# Arduino-Pro-v16_No-Silk.net
KiCad netlist of a schematic drawn in EAGLE
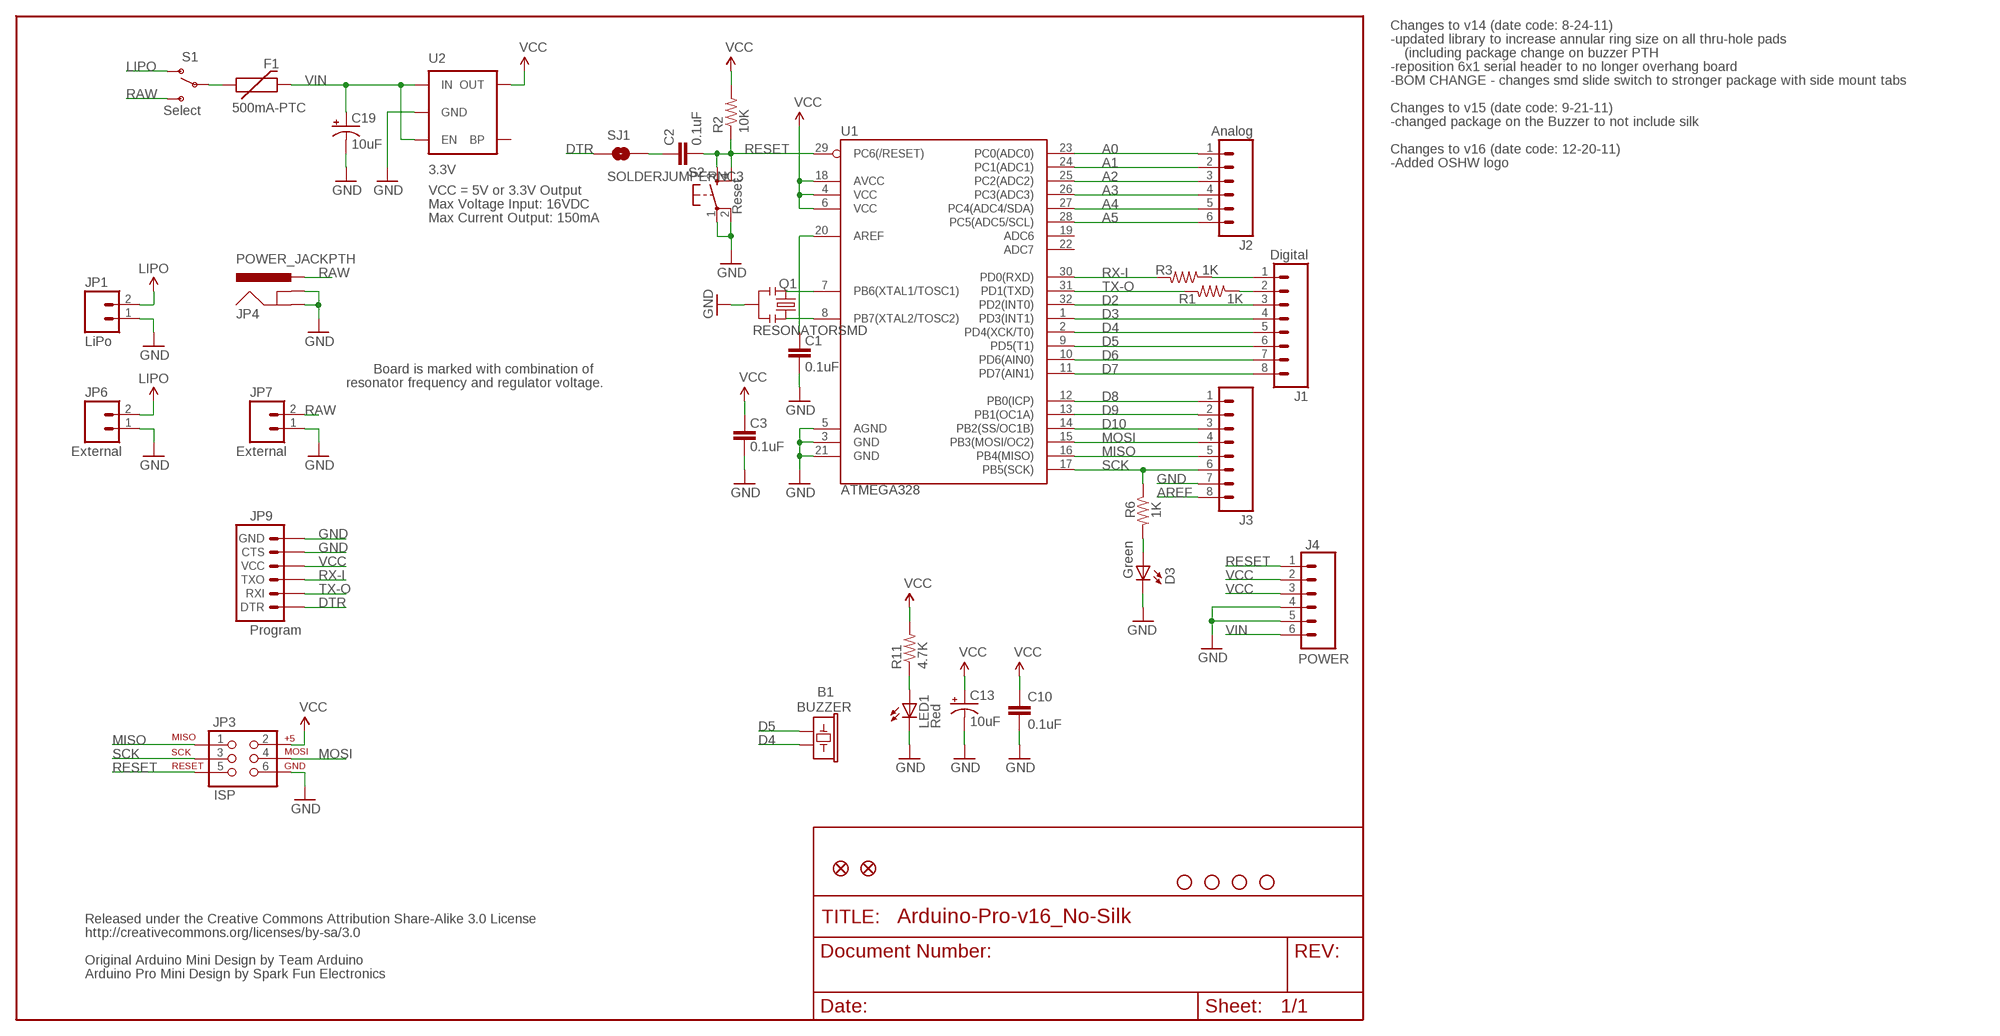
[diagram p0: schematic, sheet 1]

(export (version "E")
  (design (tool "Eeschema 10.0.6"))
  (components
    (comp (ref "B1")
      (value "BUZZER")
      (footprint "eagle-import:BUZZER-12MM-NS-KIT")
      (libsource (lib "eagle-import") (part "BUZZERPTH-NS-KIT"))
    )
    (comp (ref "C1")
      (value "0.1uF")
      (footprint "eagle-import:0402-CAP")
      (libsource (lib "eagle-import") (part "CAP0402-CAP"))
    )
    (comp (ref "C2")
      (value "0.1uF")
      (footprint "eagle-import:0402-CAP")
      (libsource (lib "eagle-import") (part "CAP0402-CAP"))
    )
    (comp (ref "C3")
      (value "0.1uF")
      (footprint "eagle-import:0402-CAP")
      (libsource (lib "eagle-import") (part "CAP0402-CAP"))
    )
    (comp (ref "C10")
      (value "0.1uF")
      (footprint "eagle-import:0402-CAP")
      (libsource (lib "eagle-import") (part "CAP0402-CAP"))
    )
    (comp (ref "C13")
      (value "10uF")
      (footprint "eagle-import:EIA3216")
      (libsource (lib "eagle-import") (part "CAP_POL1206"))
    )
    (comp (ref "C19")
      (value "10uF")
      (footprint "eagle-import:EIA3216")
      (libsource (lib "eagle-import") (part "CAP_POL1206"))
    )
    (comp (ref "D3")
      (value "Green")
      (footprint "eagle-import:LED-0603")
      (libsource (lib "eagle-import") (part "LED0603"))
    )
    (comp (ref "F1")
      (value "500mA-PTC")
      (footprint "eagle-import:PTC-1206")
      (libsource (lib "eagle-import") (part "PTCSMD"))
    )
    (comp (ref "J1")
      (value "Digital")
      (footprint "eagle-import:1X08")
      (libsource (lib "eagle-import") (part "M081X08"))
    )
    (comp (ref "J2")
      (value "Analog")
      (footprint "eagle-import:1X06")
      (libsource (lib "eagle-import") (part "M06SIP"))
    )
    (comp (ref "J3")
      (value "M081X08")
      (footprint "eagle-import:1X08")
      (libsource (lib "eagle-import") (part "M081X08"))
    )
    (comp (ref "J4")
      (value "POWER")
      (footprint "eagle-import:1X06")
      (libsource (lib "eagle-import") (part "M06SIP"))
    )
    (comp (ref "JP1")
      (value "LiPo")
      (footprint "eagle-import:JST-2-SMD")
      (libsource (lib "eagle-import") (part "M02-JST-2MM-SMT"))
    )
    (comp (ref "JP2")
      (value "FIDUCIAL1X2.5")
      (footprint "eagle-import:FIDUCIAL-1X2.5")
      (libsource (lib "eagle-import") (part "FIDUCIAL1X2.5"))
    )
    (comp (ref "JP3")
      (value "ISP")
      (footprint "eagle-import:2X3")
      (libsource (lib "eagle-import") (part "AVR_SPI_PRG_6PTH"))
    )
    (comp (ref "JP4")
      (value "POWER_JACKPTH")
      (footprint "eagle-import:POWER_JACK_PTH")
      (libsource (lib "eagle-import") (part "POWER_JACKPTH"))
    )
    (comp (ref "JP5")
      (value "FIDUCIAL1X2.5")
      (footprint "eagle-import:FIDUCIAL-1X2.5")
      (libsource (lib "eagle-import") (part "FIDUCIAL1X2.5"))
    )
    (comp (ref "JP6")
      (value "External")
      (footprint "eagle-import:1X02")
      (libsource (lib "eagle-import") (part "M02PTH"))
    )
    (comp (ref "JP7")
      (value "External")
      (footprint "eagle-import:1X02")
      (libsource (lib "eagle-import") (part "M02PTH"))
    )
    (comp (ref "JP9")
      (value "Program")
      (footprint "eagle-import:1X06-SMD")
      (libsource (lib "eagle-import") (part "ARDUINO_SERIAL_PROGRAMSMD"))
    )
    (comp (ref "LED1")
      (value "Red")
      (footprint "eagle-import:LED-0603")
      (libsource (lib "eagle-import") (part "LED0603"))
    )
    (comp (ref "Q1")
      (value "RESONATORSMD")
      (footprint "eagle-import:RESONATOR-SMD")
      (libsource (lib "eagle-import") (part "RESONATORSMD"))
    )
    (comp (ref "R1")
      (value "1K")
      (footprint "eagle-import:0402-RES")
      (libsource (lib "eagle-import") (part "RESISTOR0402-RES"))
    )
    (comp (ref "R2")
      (value "10K")
      (footprint "eagle-import:0402-RES")
      (libsource (lib "eagle-import") (part "RESISTOR0402-RES"))
    )
    (comp (ref "R3")
      (value "1K")
      (footprint "eagle-import:0402-RES")
      (libsource (lib "eagle-import") (part "RESISTOR0402-RES"))
    )
    (comp (ref "R6")
      (value "1K")
      (footprint "eagle-import:0402-RES")
      (libsource (lib "eagle-import") (part "RESISTOR0402-RES"))
    )
    (comp (ref "R11")
      (value "4.7K")
      (footprint "eagle-import:0402-RES")
      (libsource (lib "eagle-import") (part "RESISTOR0402-RES"))
    )
    (comp (ref "S1")
      (value "Select")
      (footprint "eagle-import:SWITCH-SPST-SMD-A")
      (libsource (lib "eagle-import") (part "SWITCH-SPST-SMD-A"))
    )
    (comp (ref "S2")
      (value "Reset")
      (footprint "eagle-import:TACTILE_SWITCH_SMD")
      (libsource (lib "eagle-import") (part "TAC_SWITCHSMD"))
    )
    (comp (ref "SJ1")
      (value "SOLDERJUMPERNC3")
      (footprint "eagle-import:SJ_2S-NOTRACE")
      (libsource (lib "eagle-import") (part "SOLDERJUMPERNC2"))
    )
    (comp (ref "U$1")
      (value "STAND-OFF")
      (footprint "eagle-import:STAND-OFF")
      (libsource (lib "eagle-import") (part "STAND-OFF"))
    )
    (comp (ref "U$3")
      (value "STAND-OFF")
      (footprint "eagle-import:STAND-OFF")
      (libsource (lib "eagle-import") (part "STAND-OFF"))
    )
    (comp (ref "U$9")
      (value "STAND-OFF")
      (footprint "eagle-import:STAND-OFF")
      (libsource (lib "eagle-import") (part "STAND-OFF"))
    )
    (comp (ref "U$10")
      (value "STAND-OFF")
      (footprint "eagle-import:STAND-OFF")
      (libsource (lib "eagle-import") (part "STAND-OFF"))
    )
    (comp (ref "U1")
      (value "ATMEGA328")
      (footprint "eagle-import:TQFP32-08")
      (libsource (lib "eagle-import") (part "ATMEGA168"))
    )
    (comp (ref "U2")
      (value "3.3V")
      (footprint "eagle-import:SOT23-5")
      (libsource (lib "eagle-import") (part "V_REG_LDOSMD"))
    )
  )
  (nets
    (net (code "1") (name "/A0") (class "Default")
      (node (ref "J2") (pin "1") (pinfunction "1_1") (pintype "passive"))
      (node (ref "U1") (pin "23") (pinfunction "PC0(ADC0)_23") (pintype "bidirectional"))
    )
    (net (code "2") (name "/A1") (class "Default")
      (node (ref "J2") (pin "2") (pinfunction "2_2") (pintype "passive"))
      (node (ref "U1") (pin "24") (pinfunction "PC1(ADC1)_24") (pintype "bidirectional"))
    )
    (net (code "3") (name "/A2") (class "Default")
      (node (ref "J2") (pin "3") (pinfunction "3_3") (pintype "passive"))
      (node (ref "U1") (pin "25") (pinfunction "PC2(ADC2)_25") (pintype "bidirectional"))
    )
    (net (code "4") (name "/A3") (class "Default")
      (node (ref "J2") (pin "4") (pinfunction "4_4") (pintype "passive"))
      (node (ref "U1") (pin "26") (pinfunction "PC3(ADC3)_26") (pintype "bidirectional"))
    )
    (net (code "5") (name "/A4") (class "Default")
      (node (ref "J2") (pin "5") (pinfunction "5_5") (pintype "passive"))
      (node (ref "U1") (pin "27") (pinfunction "PC4(ADC4/SDA)_27") (pintype "bidirectional"))
    )
    (net (code "6") (name "/A5") (class "Default")
      (node (ref "J2") (pin "6") (pinfunction "6_6") (pintype "passive"))
      (node (ref "U1") (pin "28") (pinfunction "PC5(ADC5/SCL)_28") (pintype "bidirectional"))
    )
    (net (code "7") (name "/AREF") (class "Default")
      (node (ref "C1") (pin "2") (pinfunction "2_2") (pintype "passive"))
      (node (ref "J3") (pin "8") (pinfunction "8_8") (pintype "passive"))
      (node (ref "U1") (pin "20") (pinfunction "AREF_20") (pintype "bidirectional"))
    )
    (net (code "8") (name "/D2") (class "Default")
      (node (ref "J1") (pin "3") (pinfunction "3_3") (pintype "passive"))
      (node (ref "U1") (pin "32") (pinfunction "PD2(INT0)_32") (pintype "bidirectional"))
    )
    (net (code "9") (name "/D3") (class "Default")
      (node (ref "J1") (pin "4") (pinfunction "4_4") (pintype "passive"))
      (node (ref "U1") (pin "1") (pinfunction "PD3(INT1)_1") (pintype "bidirectional"))
    )
    (net (code "10") (name "/D4") (class "Default")
      (node (ref "B1") (pin "-") (pinfunction "2_-") (pintype "passive"))
      (node (ref "J1") (pin "5") (pinfunction "5_5") (pintype "passive"))
      (node (ref "U1") (pin "2") (pinfunction "PD4(XCK/T0)_2") (pintype "bidirectional"))
    )
    (net (code "11") (name "/D5") (class "Default")
      (node (ref "B1") (pin "+") (pinfunction "1_+") (pintype "passive"))
      (node (ref "J1") (pin "6") (pinfunction "6_6") (pintype "passive"))
      (node (ref "U1") (pin "9") (pinfunction "PD5(T1)_9") (pintype "bidirectional"))
    )
    (net (code "12") (name "/D6") (class "Default")
      (node (ref "J1") (pin "7") (pinfunction "7_7") (pintype "passive"))
      (node (ref "U1") (pin "10") (pinfunction "PD6(AIN0)_10") (pintype "bidirectional"))
    )
    (net (code "13") (name "/D7") (class "Default")
      (node (ref "J1") (pin "8") (pinfunction "8_8") (pintype "passive"))
      (node (ref "U1") (pin "11") (pinfunction "PD7(AIN1)_11") (pintype "bidirectional"))
    )
    (net (code "14") (name "/D8") (class "Default")
      (node (ref "J3") (pin "1") (pinfunction "1_1") (pintype "passive"))
      (node (ref "U1") (pin "12") (pinfunction "PB0(ICP)_12") (pintype "bidirectional"))
    )
    (net (code "15") (name "/D9") (class "Default")
      (node (ref "J3") (pin "2") (pinfunction "2_2") (pintype "passive"))
      (node (ref "U1") (pin "13") (pinfunction "PB1(OC1A)_13") (pintype "bidirectional"))
    )
    (net (code "16") (name "/D10") (class "Default")
      (node (ref "J3") (pin "3") (pinfunction "3_3") (pintype "passive"))
      (node (ref "U1") (pin "14") (pinfunction "PB2(SS/OC1B)_14") (pintype "bidirectional"))
    )
    (net (code "17") (name "/DTR") (class "Default")
      (node (ref "JP9") (pin "1") (pinfunction "DTR_1") (pintype "passive"))
      (node (ref "SJ1") (pin "1") (pinfunction "1_1") (pintype "passive"))
    )
    (net (code "18") (name "/MISO") (class "Default")
      (node (ref "J3") (pin "5") (pinfunction "5_5") (pintype "passive"))
      (node (ref "JP3") (pin "1") (pinfunction "1_1") (pintype "passive"))
      (node (ref "U1") (pin "16") (pinfunction "PB4(MISO)_16") (pintype "bidirectional"))
    )
    (net (code "19") (name "/MOSI") (class "Default")
      (node (ref "J3") (pin "4") (pinfunction "4_4") (pintype "passive"))
      (node (ref "JP3") (pin "4") (pinfunction "4_4") (pintype "passive"))
      (node (ref "U1") (pin "15") (pinfunction "PB3(MOSI/OC2)_15") (pintype "bidirectional"))
    )
    (net (code "20") (name "/RAW") (class "Default")
      (node (ref "JP4") (pin "PWR") (pinfunction "PWR_PWR") (pintype "bidirectional"))
      (node (ref "JP7") (pin "2") (pinfunction "2_2") (pintype "passive"))
      (node (ref "S1") (pin "3") (pinfunction "S_3") (pintype "passive"))
    )
    (net (code "21") (name "/RESET") (class "Default")
      (node (ref "C2") (pin "2") (pinfunction "2_2") (pintype "passive"))
      (node (ref "J4") (pin "1") (pinfunction "1_1") (pintype "passive"))
      (node (ref "JP3") (pin "5") (pinfunction "5_5") (pintype "passive"))
      (node (ref "R2") (pin "1") (pinfunction "1_1") (pintype "passive"))
      (node (ref "S2") (pin "3") (pinfunction "3_3") (pintype "passive"))
      (node (ref "S2") (pin "4") (pinfunction "4_4") (pintype "passive"))
      (node (ref "U1") (pin "29") (pinfunction "PC6(/RESET)_29") (pintype "bidirectional"))
    )
    (net (code "22") (name "/RX-I") (class "Default")
      (node (ref "JP9") (pin "3") (pinfunction "TXO_3") (pintype "passive"))
      (node (ref "R3") (pin "2") (pinfunction "2_2") (pintype "passive"))
      (node (ref "U1") (pin "30") (pinfunction "PD0(RXD)_30") (pintype "bidirectional"))
    )
    (net (code "23") (name "/SCK") (class "Default")
      (node (ref "J3") (pin "6") (pinfunction "6_6") (pintype "passive"))
      (node (ref "JP3") (pin "3") (pinfunction "3_3") (pintype "passive"))
      (node (ref "R6") (pin "1") (pinfunction "1_1") (pintype "passive"))
      (node (ref "U1") (pin "17") (pinfunction "PB5(SCK)_17") (pintype "bidirectional"))
    )
    (net (code "24") (name "/TX-O") (class "Default")
      (node (ref "JP9") (pin "2") (pinfunction "RXI_2") (pintype "passive"))
      (node (ref "R1") (pin "2") (pinfunction "2_2") (pintype "passive"))
      (node (ref "U1") (pin "31") (pinfunction "PD1(TXD)_31") (pintype "bidirectional"))
    )
    (net (code "25") (name "/VIN") (class "Default")
      (node (ref "C19") (pin "A") (pinfunction "+_A") (pintype "passive"))
      (node (ref "F1") (pin "2") (pinfunction "2_2") (pintype "bidirectional"))
      (node (ref "J4") (pin "6") (pinfunction "6_6") (pintype "passive"))
      (node (ref "U2") (pin "1") (pinfunction "IN_1") (pintype "input"))
      (node (ref "U2") (pin "3") (pinfunction "EN_3") (pintype "input"))
    )
    (net (code "26") (name "GND") (class "Default")
      (node (ref "C1") (pin "1") (pinfunction "1_1") (pintype "passive"))
      (node (ref "C10") (pin "2") (pinfunction "2_2") (pintype "passive"))
      (node (ref "C13") (pin "C") (pinfunction "-_C") (pintype "passive"))
      (node (ref "C19") (pin "C") (pinfunction "-_C") (pintype "passive"))
      (node (ref "C3") (pin "1") (pinfunction "1_1") (pintype "passive"))
      (node (ref "D3") (pin "C") (pinfunction "C_C") (pintype "passive"))
      (node (ref "J3") (pin "7") (pinfunction "7_7") (pintype "passive"))
      (node (ref "J4") (pin "4") (pinfunction "4_4") (pintype "passive"))
      (node (ref "J4") (pin "5") (pinfunction "5_5") (pintype "passive"))
      (node (ref "JP1") (pin "1") (pinfunction "1_1") (pintype "passive"))
      (node (ref "JP3") (pin "6") (pinfunction "6_6") (pintype "passive"))
      (node (ref "JP4") (pin "GND") (pinfunction "GND_GND") (pintype "bidirectional"))
      (node (ref "JP4") (pin "GNDBREAK") (pinfunction "GNDBREAK_GNDBREAK") (pintype "bidirectional"))
      (node (ref "JP6") (pin "1") (pinfunction "1_1") (pintype "passive"))
      (node (ref "JP7") (pin "1") (pinfunction "1_1") (pintype "passive"))
      (node (ref "JP9") (pin "5") (pinfunction "CTS_5") (pintype "passive"))
      (node (ref "JP9") (pin "6") (pinfunction "GND_6") (pintype "passive"))
      (node (ref "LED1") (pin "C") (pinfunction "C_C") (pintype "passive"))
      (node (ref "Q1") (pin "2") (pinfunction "2_2") (pintype "passive"))
      (node (ref "S2") (pin "1") (pinfunction "1_1") (pintype "passive"))
      (node (ref "S2") (pin "2") (pinfunction "2_2") (pintype "passive"))
      (node (ref "U1") (pin "21") (pinfunction "GND_21") (pintype "bidirectional"))
      (node (ref "U1") (pin "3") (pinfunction "GND_3") (pintype "bidirectional"))
      (node (ref "U1") (pin "5") (pinfunction "AGND_5") (pintype "bidirectional"))
      (node (ref "U2") (pin "2") (pinfunction "GND_2") (pintype "input"))
    )
    (net (code "27") (name "LIPO") (class "Default")
      (node (ref "JP1") (pin "2") (pinfunction "2_2") (pintype "passive"))
      (node (ref "JP6") (pin "2") (pinfunction "2_2") (pintype "passive"))
      (node (ref "S1") (pin "1") (pinfunction "O_1") (pintype "passive"))
    )
    (net (code "28") (name "Net-(C2-Pad1)") (class "Default")
      (node (ref "C2") (pin "1") (pinfunction "1_1") (pintype "passive"))
      (node (ref "SJ1") (pin "2") (pinfunction "2_2") (pintype "passive"))
    )
    (net (code "29") (name "Net-(D3-PadA)") (class "Default")
      (node (ref "D3") (pin "A") (pinfunction "A_A") (pintype "passive"))
      (node (ref "R6") (pin "2") (pinfunction "2_2") (pintype "passive"))
    )
    (net (code "30") (name "Net-(J1-Pad1)") (class "Default")
      (node (ref "J1") (pin "1") (pinfunction "1_1") (pintype "passive"))
      (node (ref "R3") (pin "1") (pinfunction "1_1") (pintype "passive"))
    )
    (net (code "31") (name "Net-(J1-Pad2)") (class "Default")
      (node (ref "J1") (pin "2") (pinfunction "2_2") (pintype "passive"))
      (node (ref "R1") (pin "1") (pinfunction "1_1") (pintype "passive"))
    )
    (net (code "32") (name "Net-(LED1-PadA)") (class "Default")
      (node (ref "LED1") (pin "A") (pinfunction "A_A") (pintype "passive"))
      (node (ref "R11") (pin "1") (pinfunction "1_1") (pintype "passive"))
    )
    (net (code "33") (name "Net-(S1-P)") (class "Default")
      (node (ref "F1") (pin "1") (pinfunction "1_1") (pintype "bidirectional"))
      (node (ref "S1") (pin "2") (pinfunction "P_2") (pintype "passive"))
    )
    (net (code "34") (name "Net-(U1-PB6(XTAL1{slash}TOSC1))") (class "Default")
      (node (ref "Q1") (pin "3") (pinfunction "3_3") (pintype "passive"))
      (node (ref "U1") (pin "7") (pinfunction "PB6(XTAL1/TOSC1)_7") (pintype "bidirectional"))
    )
    (net (code "35") (name "Net-(U1-PB7(XTAL2{slash}TOSC2))") (class "Default")
      (node (ref "Q1") (pin "1") (pinfunction "1_1") (pintype "passive"))
      (node (ref "U1") (pin "8") (pinfunction "PB7(XTAL2/TOSC2)_8") (pintype "bidirectional"))
    )
    (net (code "36") (name "VCC") (class "Default")
      (node (ref "C10") (pin "1") (pinfunction "1_1") (pintype "passive"))
      (node (ref "C13") (pin "A") (pinfunction "+_A") (pintype "passive"))
      (node (ref "C3") (pin "2") (pinfunction "2_2") (pintype "passive"))
      (node (ref "J4") (pin "2") (pinfunction "2_2") (pintype "passive"))
      (node (ref "J4") (pin "3") (pinfunction "3_3") (pintype "passive"))
      (node (ref "JP3") (pin "2") (pinfunction "2_2") (pintype "passive"))
      (node (ref "JP9") (pin "4") (pinfunction "VCC_4") (pintype "passive"))
      (node (ref "R11") (pin "2") (pinfunction "2_2") (pintype "passive"))
      (node (ref "R2") (pin "2") (pinfunction "2_2") (pintype "passive"))
      (node (ref "U1") (pin "18") (pinfunction "AVCC_18") (pintype "bidirectional"))
      (node (ref "U1") (pin "4") (pinfunction "VCC_4") (pintype "bidirectional"))
      (node (ref "U1") (pin "6") (pinfunction "VCC_6") (pintype "bidirectional"))
      (node (ref "U2") (pin "5") (pinfunction "OUT_5") (pintype "passive"))
    )
    (net (code "37") (name "unconnected-(U1-ADC6-Pad19)") (class "Default")
      (node (ref "U1") (pin "19") (pinfunction "ADC6_19") (pintype "bidirectional"))
    )
    (net (code "38") (name "unconnected-(U1-ADC7-Pad22)") (class "Default")
      (node (ref "U1") (pin "22") (pinfunction "ADC7_22") (pintype "bidirectional"))
    )
    (net (code "39") (name "unconnected-(U2-BP-Pad4)") (class "Default")
      (node (ref "U2") (pin "4") (pinfunction "BP_4") (pintype "input"))
    )
  )
)
